# Assistant_Parameters.net
KiCad netlist of a schematic drawn in Altium Designer
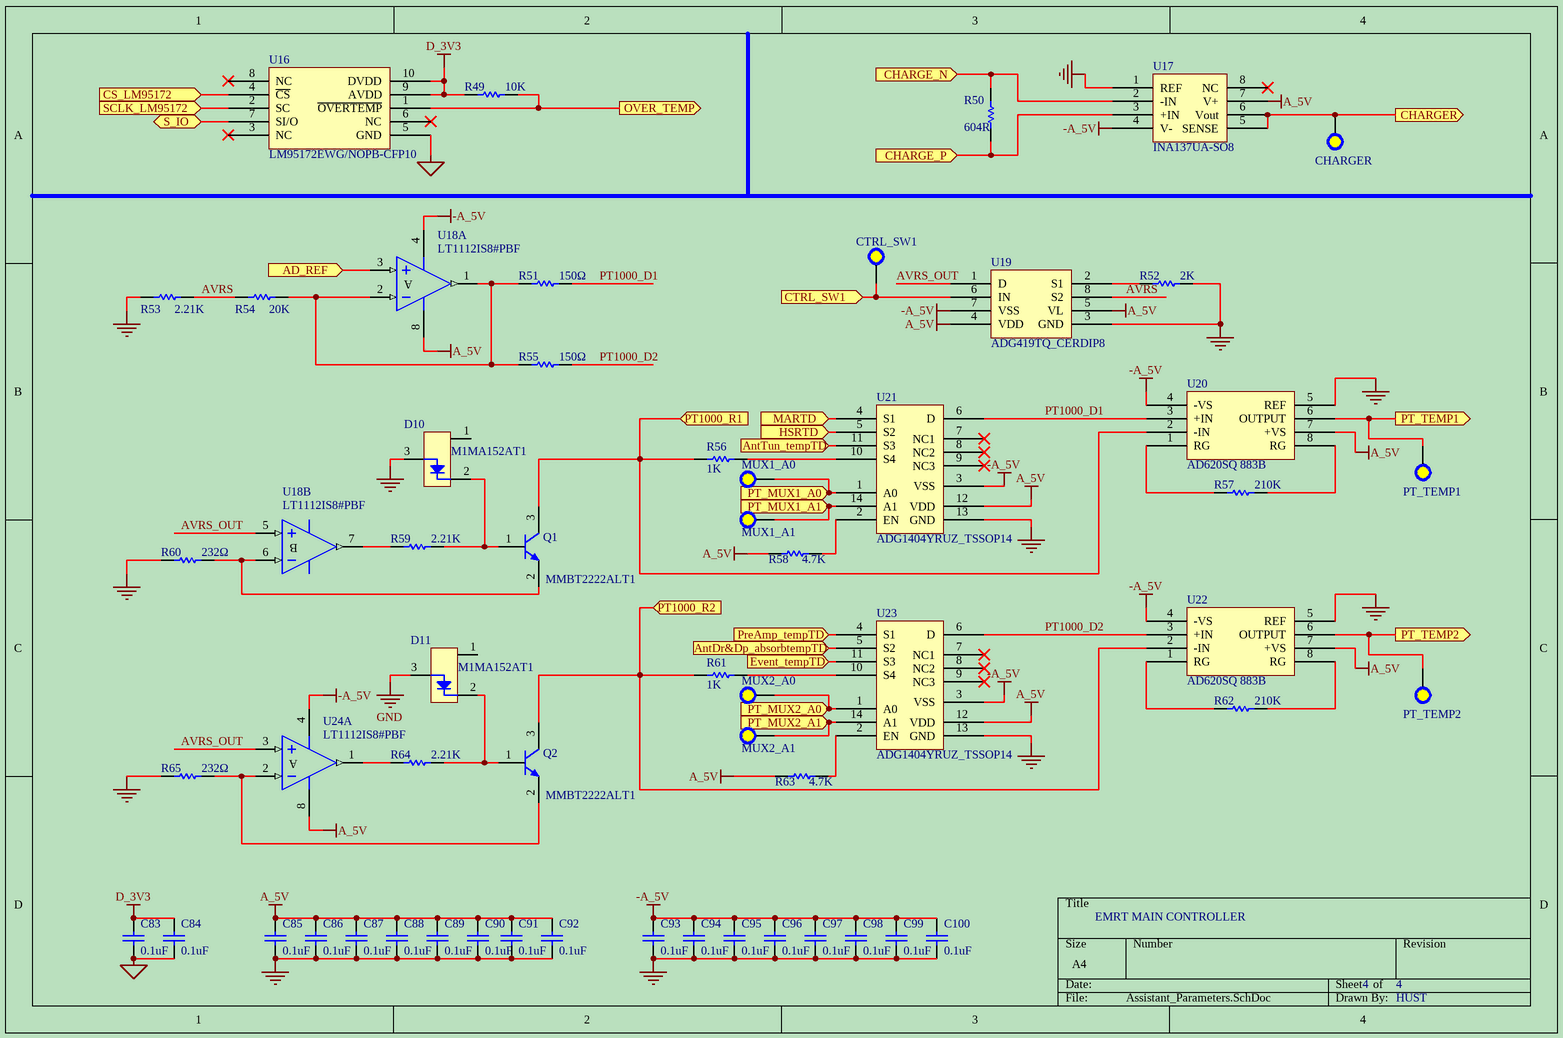
[diagram p0: Assistant_Parameters.SchDoc]

(export (version "E")
  (design (tool "Eeschema 10.0.6"))
  (components
    (comp (ref "C83")
      (value "0.1uF")
      (footprint "CAPS0805_57")
      (description "Capacitor")
      (fields (field (name "PART NUMBER") "Y20025084") (field (name "Comment") "Cap"))
      (libsource (lib "Cap") (part "Cap"))
    )
    (comp (ref "C84")
      (value "0.1uF")
      (footprint "CAPS0805_57")
      (description "Capacitor")
      (fields (field (name "PART NUMBER") "Y20025084") (field (name "Comment") "Cap"))
      (libsource (lib "Cap") (part "Cap"))
    )
    (comp (ref "C85")
      (value "0.1uF")
      (footprint "CAPS0805_57")
      (description "Capacitor")
      (fields (field (name "PART NUMBER") "Y20024100") (field (name "Comment") "Cap"))
      (libsource (lib "电容") (part "Y20024100"))
    )
    (comp (ref "C86")
      (value "Cap")
      (footprint "CAPS0805_57")
      (description "Capacitor")
      (fields (field (name "PART NUMBER") "Y20002409") (field (name "ALTIUM_UNNAMED_8") "0.1uF"))
      (libsource (lib "电容") (part "Y20002409"))
    )
    (comp (ref "C87")
      (value "0.1uF")
      (footprint "CAPS0805_57")
      (description "Capacitor")
      (fields (field (name "PART NUMBER") "Y20025084") (field (name "Comment") "Cap"))
      (libsource (lib "Cap") (part "Cap"))
    )
    (comp (ref "C88")
      (value "0.1uF")
      (footprint "CAPS0805_57")
      (description "Capacitor")
      (fields (field (name "PART NUMBER") "Y20024100") (field (name "Comment") "Cap"))
      (libsource (lib "电容") (part "Y20024100"))
    )
    (comp (ref "C89")
      (value "0.1uF")
      (footprint "CAPS0805_57")
      (description "Capacitor")
      (fields (field (name "PART NUMBER") "Y20024100") (field (name "Comment") "Cap"))
      (libsource (lib "电容") (part "Y20024100"))
    )
    (comp (ref "C90")
      (value "0.1uF")
      (footprint "CAPS0805_57")
      (description "Capacitor")
      (fields (field (name "PART NUMBER") "Y20024100") (field (name "Comment") "Cap"))
      (libsource (lib "电容") (part "Y20024100"))
    )
    (comp (ref "C91")
      (value "0.1uF")
      (footprint "CAPS0805_57")
      (description "Capacitor")
      (fields (field (name "PART NUMBER") "Y20024100") (field (name "Comment") "Cap"))
      (libsource (lib "电容") (part "Y20024100"))
    )
    (comp (ref "C92")
      (value "0.1uF")
      (footprint "CAPS0805_57")
      (description "Capacitor")
      (fields (field (name "PART NUMBER") "Y20024100") (field (name "Comment") "Cap"))
      (libsource (lib "电容") (part "Y20024100"))
    )
    (comp (ref "C93")
      (value "0.1uF")
      (footprint "CAPS0805_57")
      (description "Capacitor")
      (fields (field (name "PART NUMBER") "Y20025084") (field (name "Comment") "Cap"))
      (libsource (lib "Cap") (part "Cap"))
    )
    (comp (ref "C94")
      (value "Cap")
      (footprint "CAPS0805_57")
      (description "Capacitor")
      (fields (field (name "PART NUMBER") "Y20002409") (field (name "ALTIUM_UNNAMED_8") "0.1uF"))
      (libsource (lib "电容") (part "Y20002409"))
    )
    (comp (ref "C95")
      (value "0.1uF")
      (footprint "CAPS0805_57")
      (description "Capacitor")
      (fields (field (name "PART NUMBER") "Y20024100") (field (name "Comment") "Cap"))
      (libsource (lib "电容") (part "Y20024100"))
    )
    (comp (ref "C96")
      (value "0.1uF")
      (footprint "CAPS0805_57")
      (description "Capacitor")
      (fields (field (name "PART NUMBER") "Y20024100") (field (name "Comment") "Cap"))
      (libsource (lib "电容") (part "Y20024100"))
    )
    (comp (ref "C97")
      (value "0.1uF")
      (footprint "CAPS0805_57")
      (description "Capacitor")
      (fields (field (name "PART NUMBER") "Y20024100") (field (name "Comment") "Cap"))
      (libsource (lib "电容") (part "Y20024100"))
    )
    (comp (ref "C98")
      (value "0.1uF")
      (footprint "CAPS0805_57")
      (description "Capacitor")
      (fields (field (name "PART NUMBER") "Y20024100") (field (name "Comment") "Cap"))
      (libsource (lib "电容") (part "Y20024100"))
    )
    (comp (ref "C99")
      (value "0.1uF")
      (footprint "CAPS0805_57")
      (description "Capacitor")
      (fields (field (name "PART NUMBER") "Y20024100") (field (name "Comment") "Cap"))
      (libsource (lib "电容") (part "Y20024100"))
    )
    (comp (ref "C100")
      (value "0.1uF")
      (footprint "CAPS0805_57")
      (description "Capacitor")
      (fields (field (name "PART NUMBER") "Y20024100") (field (name "Comment") "Cap"))
      (libsource (lib "电容") (part "Y20024100"))
    )
    (comp (ref "CHARGER")
      (value "TEST_SMALL")
      (footprint "test_small")
      (libsource (lib "srj") (part "TEST_SMALL"))
    )
    (comp (ref "CTRL_SW1")
      (value "TEST_SMALL")
      (footprint "test_small")
      (libsource (lib "srj") (part "TEST_SMALL"))
    )
    (comp (ref "D10")
      (value "M1MA152AT1")
      (footprint "SC-59")
      (fields (field (name "PART NUMBER") "Y20032999"))
      (libsource (lib "MC-HT") (part "M1MA152AT1"))
    )
    (comp (ref "D11")
      (value "M1MA152AT1")
      (footprint "SC-59")
      (fields (field (name "PART NUMBER") "Y20032999"))
      (libsource (lib "MC-HT") (part "M1MA152AT1"))
    )
    (comp (ref "MUX1_A0")
      (value "TEST_SMALL")
      (footprint "test_small")
      (libsource (lib "srj") (part "TEST_SMALL"))
    )
    (comp (ref "MUX1_A1")
      (value "TEST_SMALL")
      (footprint "test_small")
      (libsource (lib "srj") (part "TEST_SMALL"))
    )
    (comp (ref "MUX2_A0")
      (value "TEST_SMALL")
      (footprint "test_small")
      (libsource (lib "srj") (part "TEST_SMALL"))
    )
    (comp (ref "MUX2_A1")
      (value "TEST_SMALL")
      (footprint "test_small")
      (libsource (lib "srj") (part "TEST_SMALL"))
    )
    (comp (ref "PT_TEMP1")
      (value "TEST_SMALL")
      (footprint "test_small")
      (libsource (lib "srj") (part "TEST_SMALL"))
    )
    (comp (ref "PT_TEMP2")
      (value "TEST_SMALL")
      (footprint "test_small")
      (libsource (lib "srj") (part "TEST_SMALL"))
    )
    (comp (ref "Q1")
      (value "MMBT2222ALT1")
      (footprint "V-PDSO_3q290×240×100_p190")
      (description "General Purpose Transistor NPN Silicon")
      (libsource (lib "MC-HT") (part "MMBT2222ALT1"))
    )
    (comp (ref "Q2")
      (value "MMBT2222ALT1")
      (footprint "V-PDSO_3q290×240×100_p190")
      (description "General Purpose Transistor NPN Silicon")
      (libsource (lib "MC-HT") (part "MMBT2222ALT1"))
    )
    (comp (ref "R49")
      (value "10K")
      (footprint "RESS0805")
      (description "Semiconductor Resistor")
      (fields
        (field (name "MANUFACTURER") "Generic Components")
        (field (name "Comment") "Res")
        (field (name "PUBLISHER") "Altium Hobart Technology Centre")
      )
      (libsource (lib "EMRT MAIN CONTROLLER") (part "Res"))
    )
    (comp (ref "R50")
      (value "604R")
      (footprint "RESS0805")
      (description "Semiconductor Resistor")
      (fields
        (field (name "MANUFACTURER") "Generic Components")
        (field (name "Comment") "Res")
        (field (name "PUBLISHER") "Altium Hobart Technology Centre")
      )
      (libsource (lib "EMRT MAIN CONTROLLER") (part "Res"))
    )
    (comp (ref "R51")
      (value "150Ω")
      (footprint "RESS0805")
      (description "Semiconductor Resistor")
      (fields
        (field (name "MANUFACTURER") "Generic Components")
        (field (name "Comment") "Res")
        (field (name "PUBLISHER") "Altium Hobart Technology Centre")
      )
      (libsource (lib "EMRT MAIN CONTROLLER") (part "Res"))
    )
    (comp (ref "R52")
      (value "2K")
      (footprint "RESS0805")
      (description "Semiconductor Resistor")
      (fields
        (field (name "MANUFACTURER") "Generic Components")
        (field (name "Comment") "Res")
        (field (name "PUBLISHER") "Altium Hobart Technology Centre")
      )
      (libsource (lib "EMRT MAIN CONTROLLER") (part "Res"))
    )
    (comp (ref "R53")
      (value "2.21K")
      (footprint "RESS0805")
      (description "Semiconductor Resistor")
      (fields
        (field (name "MANUFACTURER") "Generic Components")
        (field (name "Comment") "Res")
        (field (name "PUBLISHER") "Altium Hobart Technology Centre")
      )
      (libsource (lib "EMRT MAIN CONTROLLER") (part "Res"))
    )
    (comp (ref "R54")
      (value "20K")
      (footprint "EMRT MAIN CONTROLLER:RESS0805")
      (description "Semiconductor Resistor")
      (fields
        (field (name "MANUFACTURER") "Generic Components")
        (field (name "Comment") "Res")
        (field (name "PUBLISHER") "Altium Hobart Technology Centre")
      )
      (libsource (lib "EMRT MAIN CONTROLLER") (part "Res"))
    )
    (comp (ref "R55")
      (value "150Ω")
      (footprint "RESS0805")
      (description "Semiconductor Resistor")
      (fields
        (field (name "MANUFACTURER") "Generic Components")
        (field (name "Comment") "Res")
        (field (name "PUBLISHER") "Altium Hobart Technology Centre")
      )
      (libsource (lib "EMRT MAIN CONTROLLER") (part "Res"))
    )
    (comp (ref "R56")
      (value "1K")
      (footprint "RESS0805")
      (description "Semiconductor Resistor")
      (fields
        (field (name "MANUFACTURER") "Generic Components")
        (field (name "Comment") "Res")
        (field (name "PUBLISHER") "Altium Hobart Technology Centre")
      )
      (libsource (lib "EMRT MAIN CONTROLLER") (part "Res"))
    )
    (comp (ref "R57")
      (value "210K")
      (footprint "RESS0805")
      (description "Semiconductor Resistor")
      (fields
        (field (name "MANUFACTURER") "Generic Components")
        (field (name "Comment") "Res")
        (field (name "PUBLISHER") "Altium Hobart Technology Centre")
      )
      (libsource (lib "EMRT MAIN CONTROLLER") (part "Res"))
    )
    (comp (ref "R58")
      (value "4.7K")
      (footprint "RESS0805")
      (description "Semiconductor Resistor")
      (fields
        (field (name "MANUFACTURER") "Generic Components")
        (field (name "Comment") "Res")
        (field (name "PUBLISHER") "Altium Hobart Technology Centre")
      )
      (libsource (lib "EMRT MAIN CONTROLLER") (part "Res"))
    )
    (comp (ref "R59")
      (value "2.21K")
      (footprint "RESS0805")
      (description "Semiconductor Resistor")
      (fields
        (field (name "MANUFACTURER") "Generic Components")
        (field (name "Comment") "Res")
        (field (name "PUBLISHER") "Altium Hobart Technology Centre")
      )
      (libsource (lib "EMRT MAIN CONTROLLER") (part "Res"))
    )
    (comp (ref "R60")
      (value "232Ω")
      (footprint "RESS0805")
      (description "Semiconductor Resistor")
      (fields
        (field (name "MANUFACTURER") "Generic Components")
        (field (name "Comment") "Res")
        (field (name "PUBLISHER") "Altium Hobart Technology Centre")
      )
      (libsource (lib "EMRT MAIN CONTROLLER") (part "Res"))
    )
    (comp (ref "R61")
      (value "1K")
      (footprint "RESS0805")
      (description "Semiconductor Resistor")
      (fields
        (field (name "MANUFACTURER") "Generic Components")
        (field (name "Comment") "Res")
        (field (name "PUBLISHER") "Altium Hobart Technology Centre")
      )
      (libsource (lib "EMRT MAIN CONTROLLER") (part "Res"))
    )
    (comp (ref "R62")
      (value "210K")
      (footprint "RESS0805")
      (description "Semiconductor Resistor")
      (fields
        (field (name "MANUFACTURER") "Generic Components")
        (field (name "Comment") "Res")
        (field (name "PUBLISHER") "Altium Hobart Technology Centre")
      )
      (libsource (lib "EMRT MAIN CONTROLLER") (part "Res"))
    )
    (comp (ref "R63")
      (value "4.7K")
      (footprint "RESS0805")
      (description "Semiconductor Resistor")
      (fields
        (field (name "MANUFACTURER") "Generic Components")
        (field (name "Comment") "Res")
        (field (name "PUBLISHER") "Altium Hobart Technology Centre")
      )
      (libsource (lib "EMRT MAIN CONTROLLER") (part "Res"))
    )
    (comp (ref "R64")
      (value "2.21K")
      (footprint "RESS0805")
      (description "Semiconductor Resistor")
      (fields
        (field (name "MANUFACTURER") "Generic Components")
        (field (name "Comment") "Res")
        (field (name "PUBLISHER") "Altium Hobart Technology Centre")
      )
      (libsource (lib "EMRT MAIN CONTROLLER") (part "Res"))
    )
    (comp (ref "R65")
      (value "232Ω")
      (footprint "RESS0805")
      (description "Semiconductor Resistor")
      (fields
        (field (name "MANUFACTURER") "Generic Components")
        (field (name "Comment") "Res")
        (field (name "PUBLISHER") "Altium Hobart Technology Centre")
      )
      (libsource (lib "EMRT MAIN CONTROLLER") (part "Res"))
    )
    (comp (ref "U16")
      (value "LM95172EWG/NOPB-CFP10")
      (footprint "SOP10")
      (libsource (lib "srj") (part "LM95172EWG/NOPB"))
    )
    (comp (ref "U17")
      (value "INA137UA-SO8")
      (footprint "PDSO_8q600×490×175_p127")
      (libsource (lib "srj") (part "INA137"))
    )
    (comp (ref "U18")
      (value "LT1112IS8#PBF")
      (footprint "PDSO_8q600×490×175_p127")
      (description "Precision, Single-Supply Dual Operational Amplifier")
      (libsource (lib "MC-HT") (part "LT1112IS8#PBF"))
    )
    (comp (ref "U19")
      (value "ADG419TQ_CERDIP8")
      (footprint "CDIP_8q405×305×200_d19_p100_i300")
      (libsource (lib "MC-HT") (part "ADG419TQ/883"))
    )
    (comp (ref "U20")
      (value "AD620SQ 883B")
      (footprint "CDIP_8q405×305×200_d19_p100_i300")
      (libsource (lib "MC-HT") (part "AD620"))
    )
    (comp (ref "U21")
      (value "ADG1404YRUZ_TSSOP14")
      (footprint "TSSOP14")
      (libsource (lib "srj") (part "ADG1404"))
    )
    (comp (ref "U22")
      (value "AD620SQ 883B")
      (footprint "CDIP_8q405×305×200_d19_p100_i300")
      (libsource (lib "MC-HT") (part "AD620"))
    )
    (comp (ref "U23")
      (value "ADG1404YRUZ_TSSOP14")
      (footprint "TSSOP14")
      (libsource (lib "srj") (part "ADG1404"))
    )
    (comp (ref "U24")
      (value "LT1112IS8#PBF")
      (footprint "PDSO_8q600×490×175_p127")
      (description "Precision, Single-Supply Dual Operational Amplifier")
      (libsource (lib "MC-HT") (part "LT1112IS8#PBF"))
    )
  )
  (nets
    (net (code "1") (name "-A_5V") (class "Default")
      (node (ref "C100") (pin "2") (pinfunction "2_2") (pintype "passive"))
      (node (ref "C93") (pin "2") (pinfunction "2_2") (pintype "passive"))
      (node (ref "C94") (pin "1") (pinfunction "1_1") (pintype "passive"))
      (node (ref "C95") (pin "2") (pinfunction "2_2") (pintype "passive"))
      (node (ref "C96") (pin "2") (pinfunction "2_2") (pintype "passive"))
      (node (ref "C97") (pin "2") (pinfunction "2_2") (pintype "passive"))
      (node (ref "C98") (pin "2") (pinfunction "2_2") (pintype "passive"))
      (node (ref "C99") (pin "2") (pinfunction "2_2") (pintype "passive"))
      (node (ref "U17") (pin "4") (pinfunction "V-_4") (pintype "passive"))
      (node (ref "U18") (pin "4") (pinfunction "V-_4") (pintype "power_in"))
      (node (ref "U19") (pin "7") (pinfunction "VSS_7") (pintype "passive"))
      (node (ref "U20") (pin "4") (pinfunction "-VS_4") (pintype "passive"))
      (node (ref "U21") (pin "3") (pinfunction "VSS_3") (pintype "passive"))
      (node (ref "U22") (pin "4") (pinfunction "-VS_4") (pintype "passive"))
      (node (ref "U23") (pin "3") (pinfunction "VSS_3") (pintype "passive"))
      (node (ref "U24") (pin "4") (pinfunction "V-_4") (pintype "power_in"))
    )
    (net (code "2") (name "/AD_REF") (class "Default")
      (node (ref "U18") (pin "3") (pinfunction "IN+_3") (pintype "input"))
    )
    (net (code "3") (name "/AVRS") (class "Default")
      (node (ref "R53") (pin "1") (pinfunction "1_1") (pintype "passive"))
      (node (ref "R54") (pin "2") (pinfunction "2_2") (pintype "passive"))
      (node (ref "U19") (pin "8") (pinfunction "S2_8") (pintype "passive"))
    )
    (net (code "4") (name "/AVRS_OUT") (class "Default")
      (node (ref "U18") (pin "5") (pinfunction "IN+_5") (pintype "input"))
      (node (ref "U19") (pin "1") (pinfunction "D_1") (pintype "passive"))
      (node (ref "U24") (pin "3") (pinfunction "IN+_3") (pintype "input"))
    )
    (net (code "5") (name "/AntDr&Dp_absorbtempTD") (class "Default")
      (node (ref "U23") (pin "5") (pinfunction "S2_5") (pintype "passive"))
    )
    (net (code "6") (name "/AntTun_tempTD") (class "Default")
      (node (ref "U21") (pin "11") (pinfunction "S3_11") (pintype "passive"))
    )
    (net (code "7") (name "/CHARGER") (class "Default")
      (node (ref "CHARGER") (pin "1") (pinfunction "1_1") (pintype "passive"))
      (node (ref "U17") (pin "5") (pinfunction "SENSE_5") (pintype "passive"))
      (node (ref "U17") (pin "6") (pinfunction "Vout_6") (pintype "passive"))
    )
    (net (code "8") (name "/CHARGE_N") (class "Default")
      (node (ref "R50") (pin "1") (pinfunction "1_1") (pintype "passive"))
      (node (ref "U17") (pin "2") (pinfunction "-IN_2") (pintype "passive"))
    )
    (net (code "9") (name "/CHARGE_P") (class "Default")
      (node (ref "R50") (pin "2") (pinfunction "2_2") (pintype "passive"))
      (node (ref "U17") (pin "3") (pinfunction "+IN_3") (pintype "passive"))
    )
    (net (code "10") (name "/CS_LM95172") (class "Default")
      (node (ref "U16") (pin "4") (pinfunction "~{CS}_4") (pintype "passive"))
    )
    (net (code "11") (name "/CTRL_SW1") (class "Default")
      (node (ref "CTRL_SW1") (pin "1") (pinfunction "1_1") (pintype "passive"))
      (node (ref "U19") (pin "6") (pinfunction "IN_6") (pintype "passive"))
    )
    (net (code "12") (name "/Event_tempTD") (class "Default")
      (node (ref "U23") (pin "11") (pinfunction "S3_11") (pintype "passive"))
    )
    (net (code "13") (name "/HSRTD") (class "Default")
      (node (ref "U21") (pin "5") (pinfunction "S2_5") (pintype "passive"))
    )
    (net (code "14") (name "/MARTD") (class "Default")
      (node (ref "U21") (pin "4") (pinfunction "S1_4") (pintype "passive"))
    )
    (net (code "15") (name "/OVER_TEMP") (class "Default")
      (node (ref "R49") (pin "1") (pinfunction "1_1") (pintype "passive"))
      (node (ref "U16") (pin "1") (pinfunction "~{OVERTEMP}_1") (pintype "passive"))
    )
    (net (code "16") (name "/PT1000_D1") (class "Default")
      (node (ref "R51") (pin "1") (pinfunction "1_1") (pintype "passive"))
      (node (ref "U20") (pin "3") (pinfunction "+IN_3") (pintype "passive"))
      (node (ref "U21") (pin "6") (pinfunction "D_6") (pintype "passive"))
    )
    (net (code "17") (name "/PT1000_D2") (class "Default")
      (node (ref "R55") (pin "1") (pinfunction "1_1") (pintype "passive"))
      (node (ref "U22") (pin "3") (pinfunction "+IN_3") (pintype "passive"))
      (node (ref "U23") (pin "6") (pinfunction "D_6") (pintype "passive"))
    )
    (net (code "18") (name "/PT1000_R1") (class "Default")
      (node (ref "Q1") (pin "3") (pinfunction "C_3") (pintype "passive"))
      (node (ref "R56") (pin "1") (pinfunction "1_1") (pintype "passive"))
      (node (ref "U20") (pin "2") (pinfunction "-IN_2") (pintype "passive"))
    )
    (net (code "19") (name "/PT1000_R2") (class "Default")
      (node (ref "Q2") (pin "3") (pinfunction "C_3") (pintype "passive"))
      (node (ref "R61") (pin "1") (pinfunction "1_1") (pintype "passive"))
      (node (ref "U22") (pin "2") (pinfunction "-IN_2") (pintype "passive"))
    )
    (net (code "20") (name "/PT_MUX1_A0") (class "Default")
      (node (ref "MUX1_A0") (pin "1") (pinfunction "1_1") (pintype "passive"))
      (node (ref "U21") (pin "1") (pinfunction "A0_1") (pintype "passive"))
    )
    (net (code "21") (name "/PT_MUX1_A1") (class "Default")
      (node (ref "MUX1_A1") (pin "1") (pinfunction "1_1") (pintype "passive"))
      (node (ref "U21") (pin "14") (pinfunction "A1_14") (pintype "passive"))
    )
    (net (code "22") (name "/PT_MUX2_A0") (class "Default")
      (node (ref "MUX2_A0") (pin "1") (pinfunction "1_1") (pintype "passive"))
      (node (ref "U23") (pin "1") (pinfunction "A0_1") (pintype "passive"))
    )
    (net (code "23") (name "/PT_MUX2_A1") (class "Default")
      (node (ref "MUX2_A1") (pin "1") (pinfunction "1_1") (pintype "passive"))
      (node (ref "U23") (pin "14") (pinfunction "A1_14") (pintype "passive"))
    )
    (net (code "24") (name "/PT_TEMP1") (class "Default")
      (node (ref "PT_TEMP1") (pin "1") (pinfunction "1_1") (pintype "passive"))
      (node (ref "U20") (pin "6") (pinfunction "OUTPUT_6") (pintype "passive"))
    )
    (net (code "25") (name "/PT_TEMP2") (class "Default")
      (node (ref "PT_TEMP2") (pin "1") (pinfunction "1_1") (pintype "passive"))
      (node (ref "U22") (pin "6") (pinfunction "OUTPUT_6") (pintype "passive"))
    )
    (net (code "26") (name "/PreAmp_tempTD") (class "Default")
      (node (ref "U23") (pin "4") (pinfunction "S1_4") (pintype "passive"))
    )
    (net (code "27") (name "/SCLK_LM95172") (class "Default")
      (node (ref "U16") (pin "2") (pinfunction "SC_2") (pintype "passive"))
    )
    (net (code "28") (name "/S_IO") (class "Default")
      (node (ref "U16") (pin "7") (pinfunction "SI/O_7") (pintype "passive"))
    )
    (net (code "29") (name "A_5V") (class "Default")
      (node (ref "C85") (pin "2") (pinfunction "2_2") (pintype "passive"))
      (node (ref "C86") (pin "1") (pinfunction "1_1") (pintype "passive"))
      (node (ref "C87") (pin "2") (pinfunction "2_2") (pintype "passive"))
      (node (ref "C88") (pin "1") (pinfunction "1_1") (pintype "passive"))
      (node (ref "C89") (pin "2") (pinfunction "2_2") (pintype "passive"))
      (node (ref "C90") (pin "2") (pinfunction "2_2") (pintype "passive"))
      (node (ref "C91") (pin "2") (pinfunction "2_2") (pintype "passive"))
      (node (ref "C92") (pin "2") (pinfunction "2_2") (pintype "passive"))
      (node (ref "R58") (pin "1") (pinfunction "1_1") (pintype "passive"))
      (node (ref "R63") (pin "1") (pinfunction "1_1") (pintype "passive"))
      (node (ref "U17") (pin "7") (pinfunction "V+_7") (pintype "passive"))
      (node (ref "U18") (pin "8") (pinfunction "V+_8") (pintype "power_in"))
      (node (ref "U19") (pin "4") (pinfunction "VDD_4") (pintype "passive"))
      (node (ref "U19") (pin "5") (pinfunction "VL_5") (pintype "passive"))
      (node (ref "U20") (pin "7") (pinfunction "+VS_7") (pintype "passive"))
      (node (ref "U21") (pin "12") (pinfunction "VDD_12") (pintype "passive"))
      (node (ref "U22") (pin "7") (pinfunction "+VS_7") (pintype "passive"))
      (node (ref "U23") (pin "12") (pinfunction "VDD_12") (pintype "passive"))
      (node (ref "U24") (pin "8") (pinfunction "V+_8") (pintype "power_in"))
    )
    (net (code "30") (name "DGND") (class "Default")
      (node (ref "C83") (pin "1") (pinfunction "1_1") (pintype "passive"))
      (node (ref "C84") (pin "1") (pinfunction "1_1") (pintype "passive"))
      (node (ref "U16") (pin "5") (pinfunction "GND_5") (pintype "passive"))
    )
    (net (code "31") (name "D_3V3") (class "Default")
      (node (ref "C83") (pin "2") (pinfunction "2_2") (pintype "passive"))
      (node (ref "C84") (pin "2") (pinfunction "2_2") (pintype "passive"))
      (node (ref "R49") (pin "2") (pinfunction "2_2") (pintype "passive"))
      (node (ref "U16") (pin "10") (pinfunction "DVDD_10") (pintype "power_in"))
      (node (ref "U16") (pin "9") (pinfunction "AVDD_9") (pintype "power_in"))
    )
    (net (code "32") (name "GND") (class "Default")
      (node (ref "C100") (pin "1") (pinfunction "1_1") (pintype "passive"))
      (node (ref "C85") (pin "1") (pinfunction "1_1") (pintype "passive"))
      (node (ref "C86") (pin "2") (pinfunction "2_2") (pintype "passive"))
      (node (ref "C87") (pin "1") (pinfunction "1_1") (pintype "passive"))
      (node (ref "C88") (pin "2") (pinfunction "2_2") (pintype "passive"))
      (node (ref "C89") (pin "1") (pinfunction "1_1") (pintype "passive"))
      (node (ref "C90") (pin "1") (pinfunction "1_1") (pintype "passive"))
      (node (ref "C91") (pin "1") (pinfunction "1_1") (pintype "passive"))
      (node (ref "C92") (pin "1") (pinfunction "1_1") (pintype "passive"))
      (node (ref "C93") (pin "1") (pinfunction "1_1") (pintype "passive"))
      (node (ref "C94") (pin "2") (pinfunction "2_2") (pintype "passive"))
      (node (ref "C95") (pin "1") (pinfunction "1_1") (pintype "passive"))
      (node (ref "C96") (pin "1") (pinfunction "1_1") (pintype "passive"))
      (node (ref "C97") (pin "1") (pinfunction "1_1") (pintype "passive"))
      (node (ref "C98") (pin "1") (pinfunction "1_1") (pintype "passive"))
      (node (ref "C99") (pin "1") (pinfunction "1_1") (pintype "passive"))
      (node (ref "D10") (pin "3") (pintype "passive"))
      (node (ref "D11") (pin "3") (pintype "passive"))
      (node (ref "R52") (pin "1") (pinfunction "1_1") (pintype "passive"))
      (node (ref "R53") (pin "2") (pinfunction "2_2") (pintype "passive"))
      (node (ref "R60") (pin "2") (pinfunction "2_2") (pintype "passive"))
      (node (ref "R65") (pin "2") (pinfunction "2_2") (pintype "passive"))
      (node (ref "U17") (pin "1") (pinfunction "REF_1") (pintype "passive"))
      (node (ref "U19") (pin "3") (pinfunction "GND_3") (pintype "passive"))
      (node (ref "U20") (pin "5") (pinfunction "REF_5") (pintype "passive"))
      (node (ref "U21") (pin "13") (pinfunction "GND_13") (pintype "passive"))
      (node (ref "U22") (pin "5") (pinfunction "REF_5") (pintype "passive"))
      (node (ref "U23") (pin "13") (pinfunction "GND_13") (pintype "passive"))
    )
    (net (code "33") (name "Net-(Q1-B)") (class "Default")
      (node (ref "D10") (pin "2") (pintype "passive"))
      (node (ref "Q1") (pin "1") (pinfunction "B_1") (pintype "passive"))
      (node (ref "R59") (pin "1") (pinfunction "1_1") (pintype "passive"))
    )
    (net (code "34") (name "Net-(Q1-E)") (class "Default")
      (node (ref "Q1") (pin "2") (pinfunction "E_2") (pintype "passive"))
      (node (ref "R60") (pin "1") (pinfunction "1_1") (pintype "passive"))
      (node (ref "U18") (pin "6") (pinfunction "IN-_6") (pintype "input"))
    )
    (net (code "35") (name "Net-(Q2-B)") (class "Default")
      (node (ref "D11") (pin "2") (pintype "passive"))
      (node (ref "Q2") (pin "1") (pinfunction "B_1") (pintype "passive"))
      (node (ref "R64") (pin "1") (pinfunction "1_1") (pintype "passive"))
    )
    (net (code "36") (name "Net-(Q2-E)") (class "Default")
      (node (ref "Q2") (pin "2") (pinfunction "E_2") (pintype "passive"))
      (node (ref "R65") (pin "1") (pinfunction "1_1") (pintype "passive"))
      (node (ref "U24") (pin "2") (pinfunction "IN-_2") (pintype "input"))
    )
    (net (code "37") (name "Net-(R57-Pad1)") (class "Default")
      (node (ref "R57") (pin "1") (pinfunction "1_1") (pintype "passive"))
      (node (ref "U20") (pin "8") (pinfunction "RG_8") (pintype "passive"))
    )
    (net (code "38") (name "Net-(R57-Pad2)") (class "Default")
      (node (ref "R57") (pin "2") (pinfunction "2_2") (pintype "passive"))
      (node (ref "U20") (pin "1") (pinfunction "RG_1") (pintype "passive"))
    )
    (net (code "39") (name "Net-(R62-Pad1)") (class "Default")
      (node (ref "R62") (pin "1") (pinfunction "1_1") (pintype "passive"))
      (node (ref "U22") (pin "8") (pinfunction "RG_8") (pintype "passive"))
    )
    (net (code "40") (name "Net-(R62-Pad2)") (class "Default")
      (node (ref "R62") (pin "2") (pinfunction "2_2") (pintype "passive"))
      (node (ref "U22") (pin "1") (pinfunction "RG_1") (pintype "passive"))
    )
    (net (code "41") (name "Net-(U18A-IN-)") (class "Default")
      (node (ref "R51") (pin "2") (pinfunction "2_2") (pintype "passive"))
      (node (ref "R54") (pin "1") (pinfunction "1_1") (pintype "passive"))
      (node (ref "R55") (pin "2") (pinfunction "2_2") (pintype "passive"))
      (node (ref "U18") (pin "1") (pinfunction "OUT_1") (pintype "output"))
      (node (ref "U18") (pin "2") (pinfunction "IN-_2") (pintype "input"))
    )
    (net (code "42") (name "Net-(U18B-OUT)") (class "Default")
      (node (ref "R59") (pin "2") (pinfunction "2_2") (pintype "passive"))
      (node (ref "U18") (pin "7") (pinfunction "OUT_7") (pintype "output"))
    )
    (net (code "43") (name "Net-(U19-S1)") (class "Default")
      (node (ref "R52") (pin "2") (pinfunction "2_2") (pintype "passive"))
      (node (ref "U19") (pin "2") (pinfunction "S1_2") (pintype "passive"))
    )
    (net (code "44") (name "Net-(U21-EN)") (class "Default")
      (node (ref "R58") (pin "2") (pinfunction "2_2") (pintype "passive"))
      (node (ref "U21") (pin "2") (pinfunction "EN_2") (pintype "passive"))
    )
    (net (code "45") (name "Net-(U21-S4)") (class "Default")
      (node (ref "R56") (pin "2") (pinfunction "2_2") (pintype "passive"))
      (node (ref "U21") (pin "10") (pinfunction "S4_10") (pintype "passive"))
    )
    (net (code "46") (name "Net-(U23-EN)") (class "Default")
      (node (ref "R63") (pin "2") (pinfunction "2_2") (pintype "passive"))
      (node (ref "U23") (pin "2") (pinfunction "EN_2") (pintype "passive"))
    )
    (net (code "47") (name "Net-(U23-S4)") (class "Default")
      (node (ref "R61") (pin "2") (pinfunction "2_2") (pintype "passive"))
      (node (ref "U23") (pin "10") (pinfunction "S4_10") (pintype "passive"))
    )
    (net (code "48") (name "Net-(U24A-OUT)") (class "Default")
      (node (ref "R64") (pin "2") (pinfunction "2_2") (pintype "passive"))
      (node (ref "U24") (pin "1") (pinfunction "OUT_1") (pintype "output"))
    )
    (net (code "49") (name "unconnected-(D10-Pad1)") (class "Default")
      (node (ref "D10") (pin "1") (pintype "passive"))
    )
    (net (code "50") (name "unconnected-(D11-Pad1)") (class "Default")
      (node (ref "D11") (pin "1") (pintype "passive"))
    )
    (net (code "51") (name "unconnected-(U16-NC-Pad3)") (class "Default")
      (node (ref "U16") (pin "3") (pinfunction "NC_3") (pintype "passive+no_connect"))
    )
    (net (code "52") (name "unconnected-(U16-NC-Pad6)") (class "Default")
      (node (ref "U16") (pin "6") (pinfunction "NC_6") (pintype "passive+no_connect"))
    )
    (net (code "53") (name "unconnected-(U16-NC-Pad8)") (class "Default")
      (node (ref "U16") (pin "8") (pinfunction "NC_8") (pintype "passive+no_connect"))
    )
    (net (code "54") (name "unconnected-(U17-NC-Pad8)") (class "Default")
      (node (ref "U17") (pin "8") (pinfunction "NC_8") (pintype "passive+no_connect"))
    )
    (net (code "55") (name "unconnected-(U21-NC1-Pad7)") (class "Default")
      (node (ref "U21") (pin "7") (pinfunction "NC1_7") (pintype "passive+no_connect"))
    )
    (net (code "56") (name "unconnected-(U21-NC2-Pad8)") (class "Default")
      (node (ref "U21") (pin "8") (pinfunction "NC2_8") (pintype "passive+no_connect"))
    )
    (net (code "57") (name "unconnected-(U21-NC3-Pad9)") (class "Default")
      (node (ref "U21") (pin "9") (pinfunction "NC3_9") (pintype "passive+no_connect"))
    )
    (net (code "58") (name "unconnected-(U23-NC1-Pad7)") (class "Default")
      (node (ref "U23") (pin "7") (pinfunction "NC1_7") (pintype "passive+no_connect"))
    )
    (net (code "59") (name "unconnected-(U23-NC2-Pad8)") (class "Default")
      (node (ref "U23") (pin "8") (pinfunction "NC2_8") (pintype "passive+no_connect"))
    )
    (net (code "60") (name "unconnected-(U23-NC3-Pad9)") (class "Default")
      (node (ref "U23") (pin "9") (pinfunction "NC3_9") (pintype "passive+no_connect"))
    )
  )
)
